# rgbled.net
KiCad netlist of a schematic drawn in EAGLE
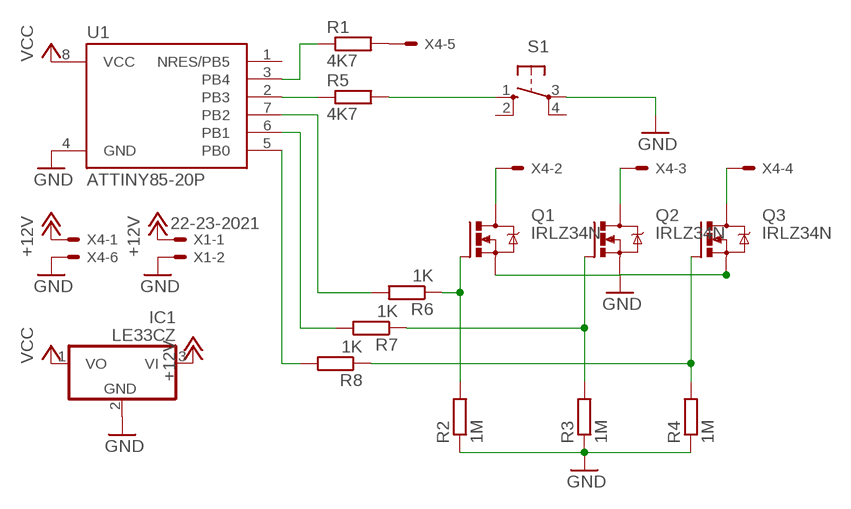
[diagram p0: schematic, sheet 1]

(export (version "E")
  (design (tool "Eeschema 10.0.6"))
  (components
    (comp (ref "IC1")
      (value "LE33CZ")
      (footprint "eagle-import:TO92")
      (libsource (lib "eagle-import") (part "78ZL05"))
    )
    (comp (ref "Q1")
      (value "IRLZ34N")
      (footprint "eagle-import:TO220BV")
      (libsource (lib "eagle-import") (part "IRF540"))
    )
    (comp (ref "Q2")
      (value "IRLZ34N")
      (footprint "eagle-import:TO220BV")
      (libsource (lib "eagle-import") (part "IRF540"))
    )
    (comp (ref "Q3")
      (value "IRLZ34N")
      (footprint "eagle-import:TO220BV")
      (libsource (lib "eagle-import") (part "IRF540"))
    )
    (comp (ref "R1")
      (value "4K7")
      (footprint "eagle-import:0204_5")
      (libsource (lib "eagle-import") (part "R-EU_0204/5"))
    )
    (comp (ref "R2")
      (value "1M")
      (footprint "eagle-import:0204_5")
      (libsource (lib "eagle-import") (part "R-EU_0204/5"))
    )
    (comp (ref "R3")
      (value "1M")
      (footprint "eagle-import:0204_5")
      (libsource (lib "eagle-import") (part "R-EU_0204/5"))
    )
    (comp (ref "R4")
      (value "1M")
      (footprint "eagle-import:0204_5")
      (libsource (lib "eagle-import") (part "R-EU_0204/5"))
    )
    (comp (ref "R5")
      (value "4K7")
      (footprint "eagle-import:0204_5")
      (libsource (lib "eagle-import") (part "R-EU_0204/5"))
    )
    (comp (ref "R6")
      (value "1K")
      (footprint "eagle-import:0204_5")
      (libsource (lib "eagle-import") (part "R-EU_0204/5"))
    )
    (comp (ref "R7")
      (value "1K")
      (footprint "eagle-import:0204_5")
      (libsource (lib "eagle-import") (part "R-EU_0204/5"))
    )
    (comp (ref "R8")
      (value "1K")
      (footprint "eagle-import:0204_5")
      (libsource (lib "eagle-import") (part "R-EU_0204/5"))
    )
    (comp (ref "S1")
      (value "10-XX")
      (footprint "eagle-import:B3F-10XX")
      (fields (field (name "MPN") "B3F-1000"))
      (libsource (lib "eagle-import") (part "10-XX"))
    )
    (comp (ref "U1")
      (value "ATTINY85-20P")
      (footprint "eagle-import:PDIP08_300MIL")
      (libsource (lib "eagle-import") (part "ATTINY85P-20"))
    )
    (comp (ref "X1")
      (value "22-23-2021")
      (footprint "eagle-import:22-23-2021")
      (fields (field (name "MF") "MOLEX"))
      (libsource (lib "eagle-import") (part "22-23-2021"))
    )
    (comp (ref "X4")
      (value "22-23-2061")
      (footprint "eagle-import:22-23-2061")
      (fields (field (name "MF") "MOLEX"))
      (libsource (lib "eagle-import") (part "22-23-2061"))
    )
  )
  (nets
    (net (code "1") (name "+12V") (class "Default")
      (node (ref "IC1") (pin "3") (pinfunction "VI_3") (pintype "input"))
      (node (ref "X1") (pin "1") (pinfunction "S_1") (pintype "passive"))
      (node (ref "X4") (pin "1") (pinfunction "S_1") (pintype "passive"))
    )
    (net (code "2") (name "GND") (class "Default")
      (node (ref "IC1") (pin "2") (pinfunction "GND_2") (pintype "passive"))
      (node (ref "Q1") (pin "S") (pinfunction "S_S") (pintype "passive"))
      (node (ref "Q2") (pin "S") (pinfunction "S_S") (pintype "passive"))
      (node (ref "Q3") (pin "S") (pinfunction "S_S") (pintype "passive"))
      (node (ref "R2") (pin "1") (pinfunction "1_1") (pintype "passive"))
      (node (ref "R3") (pin "1") (pinfunction "1_1") (pintype "passive"))
      (node (ref "R4") (pin "1") (pinfunction "1_1") (pintype "passive"))
      (node (ref "S1") (pin "3") (pinfunction "P_3") (pintype "passive"))
      (node (ref "U1") (pin "4") (pinfunction "GND_4") (pintype "power_in"))
      (node (ref "X1") (pin "2") (pinfunction "S_2") (pintype "passive"))
      (node (ref "X4") (pin "6") (pinfunction "S_6") (pintype "passive"))
    )
    (net (code "3") (name "Net-(Q1-PadG)") (class "Default")
      (node (ref "Q1") (pin "G") (pinfunction "G_G") (pintype "passive"))
      (node (ref "R2") (pin "2") (pinfunction "2_2") (pintype "passive"))
      (node (ref "R6") (pin "1") (pinfunction "1_1") (pintype "passive"))
    )
    (net (code "4") (name "Net-(Q2-PadG)") (class "Default")
      (node (ref "Q2") (pin "G") (pinfunction "G_G") (pintype "passive"))
      (node (ref "R3") (pin "2") (pinfunction "2_2") (pintype "passive"))
      (node (ref "R7") (pin "1") (pinfunction "1_1") (pintype "passive"))
    )
    (net (code "5") (name "Net-(Q3-PadG)") (class "Default")
      (node (ref "Q3") (pin "G") (pinfunction "G_G") (pintype "passive"))
      (node (ref "R4") (pin "2") (pinfunction "2_2") (pintype "passive"))
      (node (ref "R8") (pin "1") (pinfunction "1_1") (pintype "passive"))
    )
    (net (code "6") (name "Net-(S1-S)") (class "Default")
      (node (ref "R5") (pin "2") (pinfunction "2_2") (pintype "passive"))
      (node (ref "S1") (pin "1") (pinfunction "S_1") (pintype "passive"))
    )
    (net (code "7") (name "Net-(U1-PB0)") (class "Default")
      (node (ref "R8") (pin "2") (pinfunction "2_2") (pintype "passive"))
      (node (ref "U1") (pin "5") (pinfunction "PB0_5") (pintype "bidirectional"))
    )
    (net (code "8") (name "Net-(U1-PB1)") (class "Default")
      (node (ref "R7") (pin "2") (pinfunction "2_2") (pintype "passive"))
      (node (ref "U1") (pin "6") (pinfunction "PB1_6") (pintype "bidirectional"))
    )
    (net (code "9") (name "Net-(U1-PB2)") (class "Default")
      (node (ref "R6") (pin "2") (pinfunction "2_2") (pintype "passive"))
      (node (ref "U1") (pin "7") (pinfunction "PB2_7") (pintype "bidirectional"))
    )
    (net (code "10") (name "Net-(U1-PB3)") (class "Default")
      (node (ref "R5") (pin "1") (pinfunction "1_1") (pintype "passive"))
      (node (ref "U1") (pin "2") (pinfunction "PB3_2") (pintype "bidirectional"))
    )
    (net (code "11") (name "Net-(U1-PB4)") (class "Default")
      (node (ref "R1") (pin "1") (pinfunction "1_1") (pintype "passive"))
      (node (ref "U1") (pin "3") (pinfunction "PB4_3") (pintype "bidirectional"))
    )
    (net (code "12") (name "Net-(X4B-S)") (class "Default")
      (node (ref "Q1") (pin "D") (pinfunction "D_D") (pintype "passive"))
      (node (ref "X4") (pin "2") (pinfunction "S_2") (pintype "passive"))
    )
    (net (code "13") (name "Net-(X4C-S)") (class "Default")
      (node (ref "Q2") (pin "D") (pinfunction "D_D") (pintype "passive"))
      (node (ref "X4") (pin "3") (pinfunction "S_3") (pintype "passive"))
    )
    (net (code "14") (name "Net-(X4D-S)") (class "Default")
      (node (ref "Q3") (pin "D") (pinfunction "D_D") (pintype "passive"))
      (node (ref "X4") (pin "4") (pinfunction "S_4") (pintype "passive"))
    )
    (net (code "15") (name "Net-(X4E-S)") (class "Default")
      (node (ref "R1") (pin "2") (pinfunction "2_2") (pintype "passive"))
      (node (ref "X4") (pin "5") (pinfunction "S_5") (pintype "passive"))
    )
    (net (code "16") (name "VCC") (class "Default")
      (node (ref "IC1") (pin "1") (pinfunction "VO_1") (pintype "passive"))
      (node (ref "U1") (pin "8") (pinfunction "VCC_8") (pintype "power_in"))
    )
    (net (code "17") (name "unconnected-(S1-P1-Pad4)") (class "Default")
      (node (ref "S1") (pin "4") (pinfunction "P1_4") (pintype "passive"))
    )
    (net (code "18") (name "unconnected-(S1-S1-Pad2)") (class "Default")
      (node (ref "S1") (pin "2") (pinfunction "S1_2") (pintype "passive"))
    )
    (net (code "19") (name "unconnected-(U1-NRES{slash}PB5-Pad1)") (class "Default")
      (node (ref "U1") (pin "1") (pinfunction "NRES/PB5_1") (pintype "bidirectional"))
    )
  )
)
